# 14_CONNECTOR.net
KiCad netlist of a schematic drawn in Altium Designer
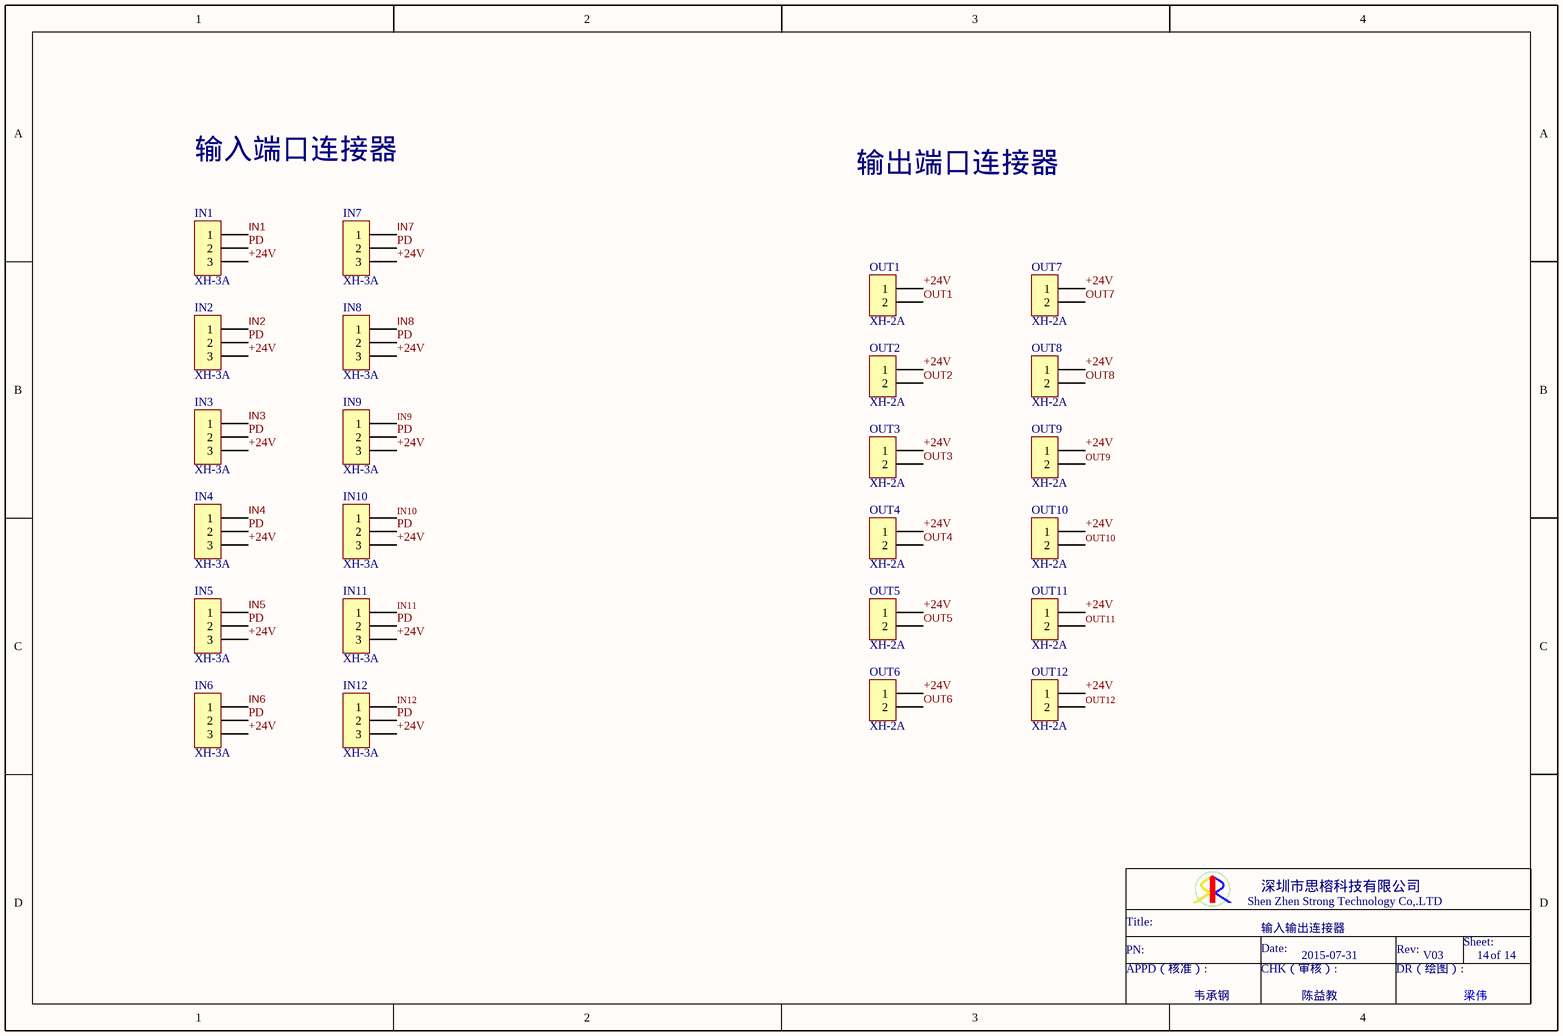
[diagram p0: 14_CONNECTOR.SchDoc]

(export (version "E")
  (design (tool "Eeschema 10.0.6"))
  (components
    (comp (ref "IN1") (value "XH-3A") (footprint "CN3-2.54") (libsource (lib "Mylibrary") (part "CON3")))
    (comp (ref "IN2") (value "XH-3A") (footprint "CN3-2.54") (libsource (lib "Mylibrary") (part "CON3")))
    (comp (ref "IN3") (value "XH-3A") (footprint "CN3-2.54") (libsource (lib "Mylibrary") (part "CON3")))
    (comp (ref "IN4") (value "XH-3A") (footprint "CN3-2.54") (libsource (lib "Mylibrary") (part "CON3")))
    (comp (ref "IN5") (value "XH-3A") (footprint "CN3-2.54") (libsource (lib "Mylibrary") (part "CON3")))
    (comp (ref "IN6") (value "XH-3A") (footprint "CN3-2.54") (libsource (lib "Mylibrary") (part "CON3")))
    (comp (ref "IN7") (value "XH-3A") (footprint "CN3-2.54") (libsource (lib "Mylibrary") (part "CON3")))
    (comp (ref "IN8") (value "XH-3A") (footprint "CN3-2.54") (libsource (lib "Mylibrary") (part "CON3")))
    (comp (ref "IN9") (value "XH-3A") (footprint "CN3-2.54") (libsource (lib "Mylibrary") (part "CON3")))
    (comp (ref "IN10") (value "XH-3A") (footprint "CN3-2.54") (libsource (lib "Mylibrary") (part "CON3")))
    (comp (ref "IN11") (value "XH-3A") (footprint "CN3-2.54") (libsource (lib "Mylibrary") (part "CON3")))
    (comp (ref "IN12") (value "XH-3A") (footprint "CN3-2.54") (libsource (lib "Mylibrary") (part "CON3")))
    (comp (ref "OUT1") (value "XH-2A") (footprint "CN2-2.54") (libsource (lib "WeiCHGSCH") (part "CON2")))
    (comp (ref "OUT2") (value "XH-2A") (footprint "CN2-2.54") (libsource (lib "WeiCHGSCH") (part "CON2")))
    (comp (ref "OUT3") (value "XH-2A") (footprint "CN2-2.54") (libsource (lib "WeiCHGSCH") (part "CON2")))
    (comp (ref "OUT4") (value "XH-2A") (footprint "CN2-2.54") (libsource (lib "WeiCHGSCH") (part "CON2")))
    (comp (ref "OUT5") (value "XH-2A") (footprint "CN2-2.54") (libsource (lib "WeiCHGSCH") (part "CON2")))
    (comp (ref "OUT6") (value "XH-2A") (footprint "CN2-2.54") (libsource (lib "WeiCHGSCH") (part "CON2")))
    (comp (ref "OUT7") (value "XH-2A") (footprint "CN2-2.54") (libsource (lib "WeiCHGSCH") (part "CON2")))
    (comp (ref "OUT8") (value "XH-2A") (footprint "CN2-2.54") (libsource (lib "WeiCHGSCH") (part "CON2")))
    (comp (ref "OUT9") (value "XH-2A") (footprint "CN2-2.54") (libsource (lib "WeiCHGSCH") (part "CON2")))
    (comp (ref "OUT10") (value "XH-2A") (footprint "CN2-2.54") (libsource (lib "WeiCHGSCH") (part "CON2")))
    (comp (ref "OUT11") (value "XH-2A") (footprint "CN2-2.54") (libsource (lib "WeiCHGSCH") (part "CON2")))
    (comp (ref "OUT12") (value "XH-2A") (footprint "CN2-2.54") (libsource (lib "WeiCHGSCH") (part "CON2")))
  )
  (nets
    (net (code "1") (name "/+24V") (class "Default")
      (node (ref "IN1") (pin "3") (pinfunction "3_3") (pintype "passive"))
      (node (ref "IN10") (pin "3") (pinfunction "3_3") (pintype "passive"))
      (node (ref "IN11") (pin "3") (pinfunction "3_3") (pintype "passive"))
      (node (ref "IN12") (pin "3") (pinfunction "3_3") (pintype "passive"))
      (node (ref "IN2") (pin "3") (pinfunction "3_3") (pintype "passive"))
      (node (ref "IN3") (pin "3") (pinfunction "3_3") (pintype "passive"))
      (node (ref "IN4") (pin "3") (pinfunction "3_3") (pintype "passive"))
      (node (ref "IN5") (pin "3") (pinfunction "3_3") (pintype "passive"))
      (node (ref "IN6") (pin "3") (pinfunction "3_3") (pintype "passive"))
      (node (ref "IN7") (pin "3") (pinfunction "3_3") (pintype "passive"))
      (node (ref "IN8") (pin "3") (pinfunction "3_3") (pintype "passive"))
      (node (ref "IN9") (pin "3") (pinfunction "3_3") (pintype "passive"))
      (node (ref "OUT1") (pin "1") (pinfunction "1_1") (pintype "passive"))
      (node (ref "OUT10") (pin "1") (pinfunction "1_1") (pintype "passive"))
      (node (ref "OUT11") (pin "1") (pinfunction "1_1") (pintype "passive"))
      (node (ref "OUT12") (pin "1") (pinfunction "1_1") (pintype "passive"))
      (node (ref "OUT2") (pin "1") (pinfunction "1_1") (pintype "passive"))
      (node (ref "OUT3") (pin "1") (pinfunction "1_1") (pintype "passive"))
      (node (ref "OUT4") (pin "1") (pinfunction "1_1") (pintype "passive"))
      (node (ref "OUT5") (pin "1") (pinfunction "1_1") (pintype "passive"))
      (node (ref "OUT6") (pin "1") (pinfunction "1_1") (pintype "passive"))
      (node (ref "OUT7") (pin "1") (pinfunction "1_1") (pintype "passive"))
      (node (ref "OUT8") (pin "1") (pinfunction "1_1") (pintype "passive"))
      (node (ref "OUT9") (pin "1") (pinfunction "1_1") (pintype "passive"))
    )
    (net (code "2") (name "/IN1") (class "Default")
      (node (ref "IN1") (pin "1") (pinfunction "1_1") (pintype "passive"))
    )
    (net (code "3") (name "/IN2") (class "Default")
      (node (ref "IN2") (pin "1") (pinfunction "1_1") (pintype "passive"))
    )
    (net (code "4") (name "/IN3") (class "Default")
      (node (ref "IN3") (pin "1") (pinfunction "1_1") (pintype "passive"))
    )
    (net (code "5") (name "/IN4") (class "Default")
      (node (ref "IN4") (pin "1") (pinfunction "1_1") (pintype "passive"))
    )
    (net (code "6") (name "/IN5") (class "Default")
      (node (ref "IN5") (pin "1") (pinfunction "1_1") (pintype "passive"))
    )
    (net (code "7") (name "/IN6") (class "Default")
      (node (ref "IN6") (pin "1") (pinfunction "1_1") (pintype "passive"))
    )
    (net (code "8") (name "/IN7") (class "Default")
      (node (ref "IN7") (pin "1") (pinfunction "1_1") (pintype "passive"))
    )
    (net (code "9") (name "/IN8") (class "Default")
      (node (ref "IN8") (pin "1") (pinfunction "1_1") (pintype "passive"))
    )
    (net (code "10") (name "/IN9") (class "Default")
      (node (ref "IN9") (pin "1") (pinfunction "1_1") (pintype "passive"))
    )
    (net (code "11") (name "/IN10") (class "Default")
      (node (ref "IN10") (pin "1") (pinfunction "1_1") (pintype "passive"))
    )
    (net (code "12") (name "/IN11") (class "Default")
      (node (ref "IN11") (pin "1") (pinfunction "1_1") (pintype "passive"))
    )
    (net (code "13") (name "/IN12") (class "Default")
      (node (ref "IN12") (pin "1") (pinfunction "1_1") (pintype "passive"))
    )
    (net (code "14") (name "/OUT1") (class "Default")
      (node (ref "OUT1") (pin "2") (pinfunction "2_2") (pintype "passive"))
    )
    (net (code "15") (name "/OUT2") (class "Default")
      (node (ref "OUT2") (pin "2") (pinfunction "2_2") (pintype "passive"))
    )
    (net (code "16") (name "/OUT3") (class "Default")
      (node (ref "OUT3") (pin "2") (pinfunction "2_2") (pintype "passive"))
    )
    (net (code "17") (name "/OUT4") (class "Default")
      (node (ref "OUT4") (pin "2") (pinfunction "2_2") (pintype "passive"))
    )
    (net (code "18") (name "/OUT5") (class "Default")
      (node (ref "OUT5") (pin "2") (pinfunction "2_2") (pintype "passive"))
    )
    (net (code "19") (name "/OUT6") (class "Default")
      (node (ref "OUT6") (pin "2") (pinfunction "2_2") (pintype "passive"))
    )
    (net (code "20") (name "/OUT7") (class "Default")
      (node (ref "OUT7") (pin "2") (pinfunction "2_2") (pintype "passive"))
    )
    (net (code "21") (name "/OUT8") (class "Default")
      (node (ref "OUT8") (pin "2") (pinfunction "2_2") (pintype "passive"))
    )
    (net (code "22") (name "/OUT9") (class "Default")
      (node (ref "OUT9") (pin "2") (pinfunction "2_2") (pintype "passive"))
    )
    (net (code "23") (name "/OUT10") (class "Default")
      (node (ref "OUT10") (pin "2") (pinfunction "2_2") (pintype "passive"))
    )
    (net (code "24") (name "/OUT11") (class "Default")
      (node (ref "OUT11") (pin "2") (pinfunction "2_2") (pintype "passive"))
    )
    (net (code "25") (name "/OUT12") (class "Default")
      (node (ref "OUT12") (pin "2") (pinfunction "2_2") (pintype "passive"))
    )
    (net (code "26") (name "/PD") (class "Default")
      (node (ref "IN1") (pin "2") (pinfunction "2_2") (pintype "passive"))
      (node (ref "IN10") (pin "2") (pinfunction "2_2") (pintype "passive"))
      (node (ref "IN11") (pin "2") (pinfunction "2_2") (pintype "passive"))
      (node (ref "IN12") (pin "2") (pinfunction "2_2") (pintype "passive"))
      (node (ref "IN2") (pin "2") (pinfunction "2_2") (pintype "passive"))
      (node (ref "IN3") (pin "2") (pinfunction "2_2") (pintype "passive"))
      (node (ref "IN4") (pin "2") (pinfunction "2_2") (pintype "passive"))
      (node (ref "IN5") (pin "2") (pinfunction "2_2") (pintype "passive"))
      (node (ref "IN6") (pin "2") (pinfunction "2_2") (pintype "passive"))
      (node (ref "IN7") (pin "2") (pinfunction "2_2") (pintype "passive"))
      (node (ref "IN8") (pin "2") (pinfunction "2_2") (pintype "passive"))
      (node (ref "IN9") (pin "2") (pinfunction "2_2") (pintype "passive"))
    )
  )
)
